# tanh_function_cell.net
KiCad netlist of a schematic drawn in Altium Designer
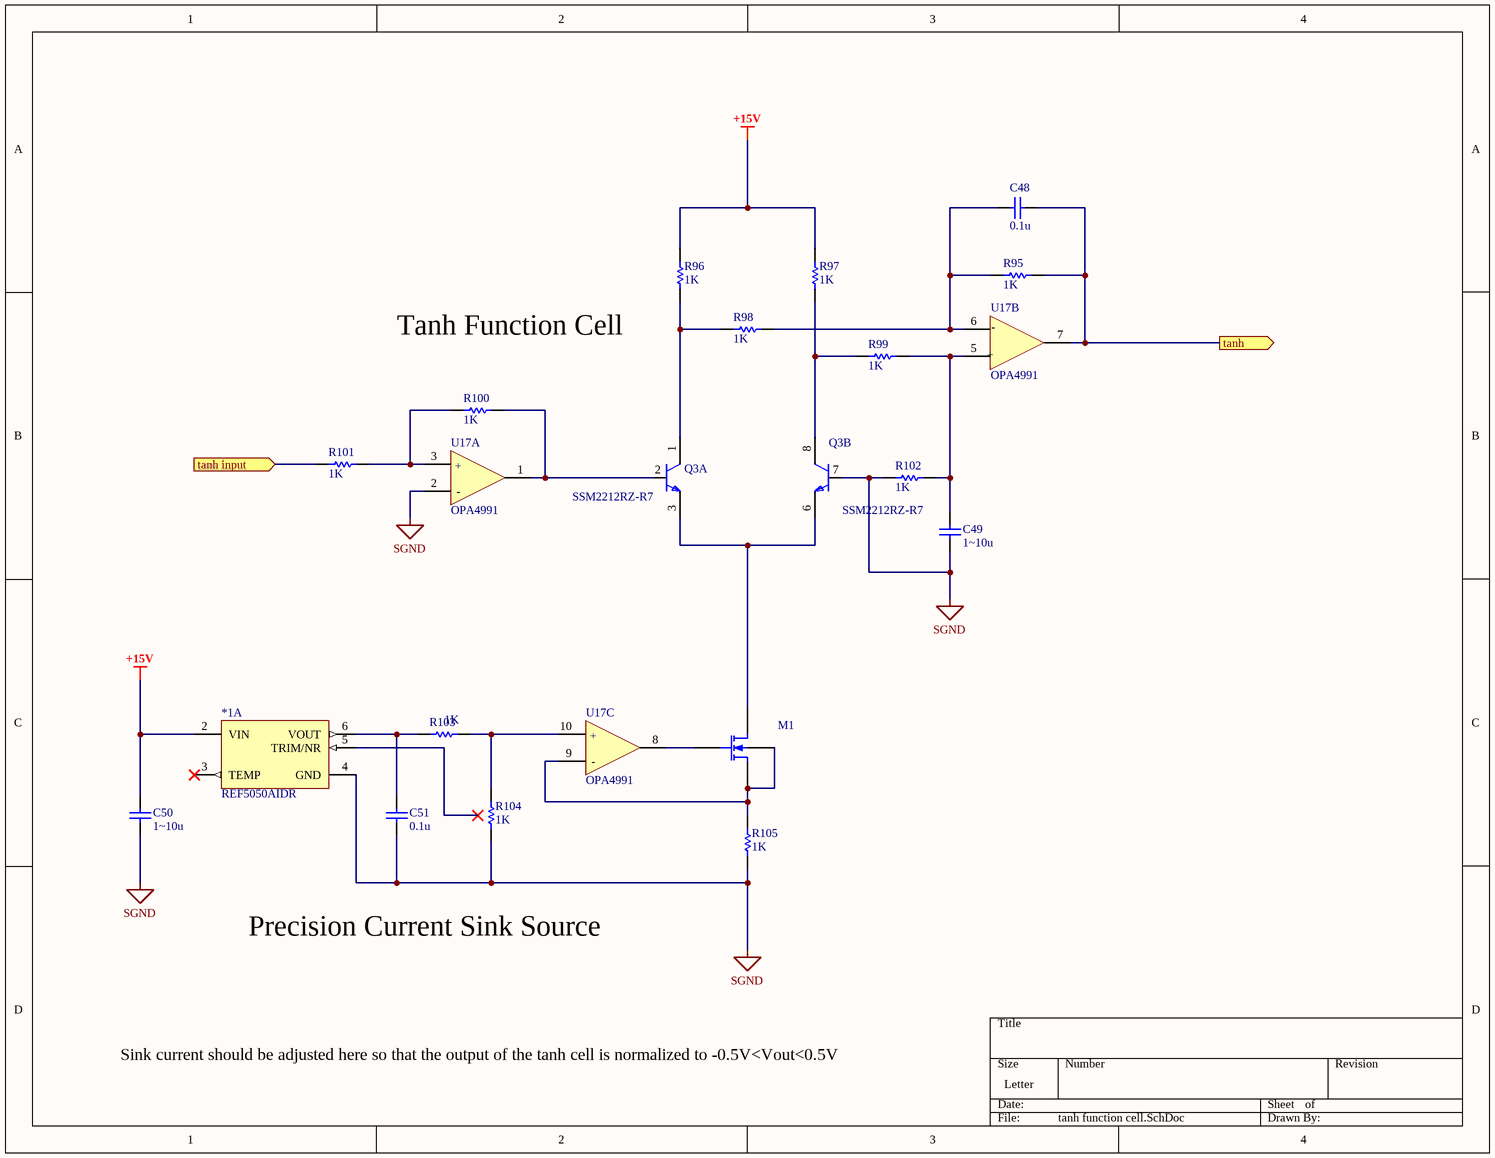
[diagram p0: tanh function cell.SchDoc]

(export (version "E")
  (design (tool "Eeschema 10.0.6"))
  (components
    (comp (ref "*1")
      (value "REF5050AIDR")
      (footprint "D0008A_M")
      (description "Three Terminal Voltage Reference, 1 Output, 5V, Trim/Adjustable, PDSO8")
      (fields (field (name "MANUFACTURER") "Texas Instruments"))
      (libsource (lib "DRC") (part "REF5050AIDR"))
    )
    (comp (ref "C48")
      (value "0.1u")
      (description "Capacitor")
      (libsource (lib "Simulation Generic Components") (part "Capacitor"))
    )
    (comp (ref "C49")
      (value "1~10u")
      (description "Capacitor")
      (libsource (lib "Simulation Generic Components") (part "Capacitor"))
    )
    (comp (ref "C50")
      (value "1~10u")
      (description "Capacitor")
      (libsource (lib "Simulation Generic Components") (part "Capacitor"))
    )
    (comp (ref "C51")
      (value "0.1u")
      (description "Capacitor")
      (libsource (lib "Simulation Generic Components") (part "Capacitor"))
    )
    (comp (ref "M1")
      (value "N-channel MOSFET BSIM4v7 v4.7.0 Model")
      (fields (field (name "XPART") "0"))
      (libsource (lib "Simulation Generic Components") (part "MOSFET N-ch Lev14_3"))
    )
    (comp (ref "Q3")
      (value "SSM2212RZ-R7")
      (footprint "FP-R-8-IPC_B")
      (description "TRANS 2NPN 40V 0.02A 8SOIC")
      (libsource (lib "") (part "SSM2212_1"))
    )
    (comp (ref "R95")
      (value "1K")
      (description "Resistor")
      (libsource (lib "Simulation Generic Components") (part "Resistor"))
    )
    (comp (ref "R96")
      (value "1K")
      (description "Resistor")
      (libsource (lib "Simulation Generic Components") (part "Resistor"))
    )
    (comp (ref "R97")
      (value "1K")
      (description "Resistor")
      (libsource (lib "Simulation Generic Components") (part "Resistor"))
    )
    (comp (ref "R98")
      (value "1K")
      (description "Resistor")
      (libsource (lib "Simulation Generic Components") (part "Resistor"))
    )
    (comp (ref "R99")
      (value "1K")
      (description "Resistor")
      (libsource (lib "Simulation Generic Components") (part "Resistor"))
    )
    (comp (ref "R100")
      (value "1K")
      (description "Resistor")
      (libsource (lib "Simulation Generic Components") (part "Resistor"))
    )
    (comp (ref "R101")
      (value "1K")
      (description "Resistor")
      (libsource (lib "Simulation Generic Components") (part "Resistor"))
    )
    (comp (ref "R102")
      (value "1K")
      (description "Resistor")
      (libsource (lib "Simulation Generic Components") (part "Resistor"))
    )
    (comp (ref "R103")
      (value "1K")
      (description "Resistor")
      (libsource (lib "Simulation Generic Components") (part "Resistor"))
    )
    (comp (ref "R104")
      (value "1K")
      (description "Resistor")
      (libsource (lib "Simulation Generic Components") (part "Resistor"))
    )
    (comp (ref "R105")
      (value "1K")
      (description "Resistor")
      (libsource (lib "Simulation Generic Components") (part "Resistor"))
    )
    (comp (ref "U17")
      (value "OPA4991")
      (footprint "FP-D0014A-IPC_B")
      (description "40-V, DUAL 4.5MHZ, RAIL-TO-RAIL")
      (libsource (lib "DRC") (part "OPA4991IDR"))
    )
  )
  (nets
    (net (code "1") (name "+15V") (class "Default")
      (node (ref "*1") (pin "2") (pinfunction "VIN_2") (pintype "power_in"))
      (node (ref "C50") (pin "2") (pinfunction "2_2") (pintype "passive"))
      (node (ref "R96") (pin "2") (pinfunction "2_2") (pintype "passive"))
      (node (ref "R97") (pin "2") (pinfunction "2_2") (pintype "passive"))
    )
    (net (code "2") (name "/tanh") (class "Default")
      (node (ref "C48") (pin "1") (pinfunction "1_1") (pintype "passive"))
      (node (ref "R95") (pin "1") (pinfunction "1_1") (pintype "passive"))
      (node (ref "U17") (pin "7") (pinfunction "OUT2_7") (pintype "passive"))
    )
    (net (code "3") (name "/tanh input") (class "Default")
      (node (ref "R101") (pin "2") (pinfunction "2_2") (pintype "passive"))
    )
    (net (code "4") (name "Net-(*1A-VOUT)") (class "Default")
      (node (ref "*1") (pin "6") (pinfunction "VOUT_6") (pintype "output"))
      (node (ref "C51") (pin "2") (pinfunction "2_2") (pintype "passive"))
      (node (ref "R103") (pin "2") (pinfunction "2_2") (pintype "passive"))
    )
    (net (code "5") (name "Net-(M1-B)") (class "Default")
      (node (ref "M1") (pin "3") (pinfunction "S_3") (pintype "passive"))
      (node (ref "M1") (pin "4") (pinfunction "B_4") (pintype "passive"))
      (node (ref "R105") (pin "2") (pinfunction "2_2") (pintype "passive"))
      (node (ref "U17") (pin "9") (pinfunction "IN3-_9") (pintype "tri_state"))
    )
    (net (code "6") (name "Net-(M1-D)") (class "Default")
      (node (ref "M1") (pin "1") (pinfunction "D_1") (pintype "passive"))
      (node (ref "Q3") (pin "3") (pinfunction "E1_3") (pintype "passive"))
      (node (ref "Q3") (pin "6") (pinfunction "E2_6") (pintype "passive"))
    )
    (net (code "7") (name "Net-(M1-G)") (class "Default")
      (node (ref "M1") (pin "2") (pinfunction "G_2") (pintype "passive"))
      (node (ref "U17") (pin "8") (pinfunction "OUT3_8") (pintype "passive"))
    )
    (net (code "8") (name "Net-(Q3A-B1)") (class "Default")
      (node (ref "Q3") (pin "2") (pinfunction "B1_2") (pintype "passive"))
      (node (ref "R100") (pin "1") (pinfunction "1_1") (pintype "passive"))
      (node (ref "U17") (pin "1") (pinfunction "OUT1_1") (pintype "passive"))
    )
    (net (code "9") (name "Net-(Q3A-C1)") (class "Default")
      (node (ref "Q3") (pin "1") (pinfunction "C1_1") (pintype "passive"))
      (node (ref "R96") (pin "1") (pinfunction "1_1") (pintype "passive"))
      (node (ref "R98") (pin "2") (pinfunction "2_2") (pintype "passive"))
    )
    (net (code "10") (name "Net-(Q3B-C2)") (class "Default")
      (node (ref "Q3") (pin "8") (pinfunction "C2_8") (pintype "passive"))
      (node (ref "R97") (pin "1") (pinfunction "1_1") (pintype "passive"))
      (node (ref "R99") (pin "2") (pinfunction "2_2") (pintype "passive"))
    )
    (net (code "11") (name "Net-(U17A-IN1+)") (class "Default")
      (node (ref "R100") (pin "2") (pinfunction "2_2") (pintype "passive"))
      (node (ref "R101") (pin "1") (pinfunction "1_1") (pintype "passive"))
      (node (ref "U17") (pin "3") (pinfunction "IN1+_3") (pintype "tri_state"))
    )
    (net (code "12") (name "Net-(U17B-IN2+)") (class "Default")
      (node (ref "C49") (pin "2") (pinfunction "2_2") (pintype "passive"))
      (node (ref "R102") (pin "2") (pinfunction "2_2") (pintype "passive"))
      (node (ref "R99") (pin "1") (pinfunction "1_1") (pintype "passive"))
      (node (ref "U17") (pin "5") (pinfunction "IN2+_5") (pintype "tri_state"))
    )
    (net (code "13") (name "Net-(U17B-IN2-)") (class "Default")
      (node (ref "C48") (pin "2") (pinfunction "2_2") (pintype "passive"))
      (node (ref "R95") (pin "2") (pinfunction "2_2") (pintype "passive"))
      (node (ref "R98") (pin "1") (pinfunction "1_1") (pintype "passive"))
      (node (ref "U17") (pin "6") (pinfunction "IN2-_6") (pintype "tri_state"))
    )
    (net (code "14") (name "Net-(U17C-IN3+)") (class "Default")
      (node (ref "R103") (pin "1") (pinfunction "1_1") (pintype "passive"))
      (node (ref "R104") (pin "1") (pinfunction "1_1") (pintype "passive"))
      (node (ref "U17") (pin "10") (pinfunction "IN3+_10") (pintype "tri_state"))
    )
    (net (code "15") (name "SGND") (class "Default")
      (node (ref "*1") (pin "4") (pinfunction "GND_4") (pintype "power_in"))
      (node (ref "C49") (pin "1") (pinfunction "1_1") (pintype "passive"))
      (node (ref "C50") (pin "1") (pinfunction "1_1") (pintype "passive"))
      (node (ref "C51") (pin "1") (pinfunction "1_1") (pintype "passive"))
      (node (ref "Q3") (pin "7") (pinfunction "B2_7") (pintype "passive"))
      (node (ref "R102") (pin "1") (pinfunction "1_1") (pintype "passive"))
      (node (ref "R104") (pin "2") (pinfunction "2_2") (pintype "passive"))
      (node (ref "R105") (pin "1") (pinfunction "1_1") (pintype "passive"))
      (node (ref "U17") (pin "2") (pinfunction "IN1-_2") (pintype "tri_state"))
    )
    (net (code "16") (name "unconnected-(*1A-TEMP-Pad3)") (class "Default")
      (node (ref "*1") (pin "3") (pinfunction "TEMP_3") (pintype "output+no_connect"))
    )
    (net (code "17") (name "unconnected-(*1A-TRIM{slash}NR-Pad5)") (class "Default")
      (node (ref "*1") (pin "5") (pinfunction "TRIM/NR_5") (pintype "input+no_connect"))
    )
  )
)
